# Power.net
KiCad netlist of a schematic drawn in Altium Designer
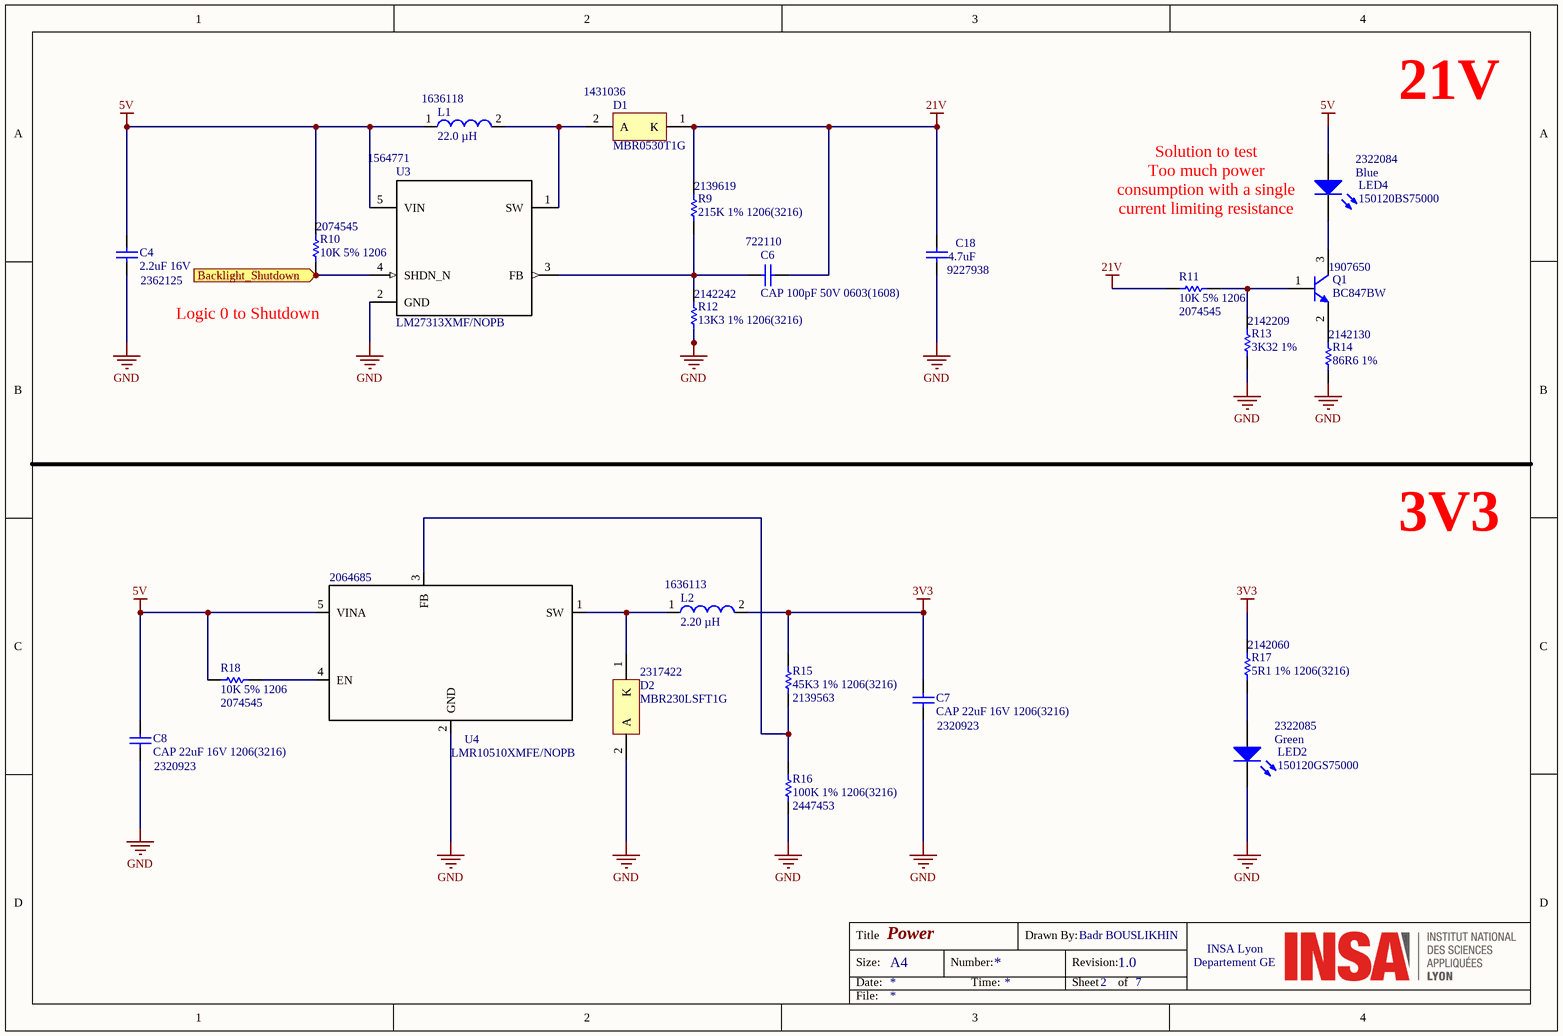
[diagram p0: Power.SchDoc]

(export (version "E")
  (design (tool "Eeschema 10.0.6"))
  (components
    (comp (ref "C4")
      (value "2.2uF 16V")
      (footprint "CAPC1206(3216)190_L")
      (description "CAP 2.2uF 16V ±20% 1206 (3216 Metric) Thickness 1.9mm SMD")
      (fields (field (name "TOLERANCE") "±20%") (field (name "SUPPLIER PART NUMBER 1") "2362125"))
      (libsource (lib "Altium Content Vault") (part "CMP-1037-04816-1"))
    )
    (comp (ref "C6")
      (value "CAP 100pF 50V 0603(1608)")
      (footprint "CAPC0603(1608)100_L")
      (description "CAP 100pF 50V ±10% 0603 (1608 Metric) Thickness 1mm SMD")
      (fields
        (field (name "TOLERANCE") "±10%")
        (field (name "SUPPLIER PART NUMBER 1") "722110")
        (field (name "MANUFACTURER") "YAGEO (PHYCOMP)")
      )
      (libsource (lib "Altium Content Vault") (part "CAP"))
    )
    (comp (ref "C7")
      (value "CAP 22uF 16V 1206(3216)")
      (footprint "CAPC1206(3216)190_N")
      (description "CAP 22uF 16V ±10% 1206 (3216 Metric) Thickness 1.9mm SMD")
      (fields (field (name "TOLERANCE") "±10%") (field (name "SUPPLIER PART NUMBER 1") "2320923"))
      (libsource (lib "Altium Content Vault") (part "CMP-1037-04992-1"))
    )
    (comp (ref "C8")
      (value "CAP 22uF 16V 1206(3216)")
      (footprint "CAPC1206(3216)190_N")
      (description "CAP 22uF 16V ±10% 1206 (3216 Metric) Thickness 1.9mm SMD")
      (fields (field (name "TOLERANCE") "±10%") (field (name "SUPPLIER PART NUMBER 1") "2320923"))
      (libsource (lib "Altium Content Vault") (part "CMP-1037-04992-1"))
    )
    (comp (ref "C18")
      (value "4.7uF")
      (footprint "CAPC1206(3216)190_N")
      (description "CAP 4.7uF 50V ±10% 1206 (3216 Metric) Thickness 1.9mm SMD")
      (fields (field (name "TOLERANCE") "±10%") (field (name "SUPPLIER PART NUMBER 1") "9227938"))
      (libsource (lib "Altium Content Vault") (part "CAP"))
    )
    (comp (ref "D1")
      (value "MBR0530T1G")
      (footprint "ONSC-SOD-123-2-425-04_V")
      (description "Schottky Power Rectifier, 2-Pin SOD-123, Pb-Free, Tape and Reel")
      (fields
        (field (name "MANUFACTURER") "On Semiconductor")
        (field (name "SUPPLIER PART NUMBER 1") "1431036")
      )
      (libsource (lib "Altium Content Vault") (part "CMP-1055-00413-1"))
    )
    (comp (ref "D2")
      (value "MBR230LSFT1G")
      (footprint "ONSC-SOD-123FL-2-498-01_V")
      (description "Schottky Power Rectifier, 2-Pin SOD-123, Pb-Free, Tape and Reel")
      (fields
        (field (name "MANUFACTURER") "On Semiconductor")
        (field (name "SUPPLIER PART NUMBER 1") "2317422")
      )
      (libsource (lib "Altium Content Vault") (part "CMP-1055-00442-1"))
    )
    (comp (ref "L1")
      (value "22.0 µH")
      (footprint "WE-PD4-S")
      (description "SMD-Power Inductor WE-PD4, L = 22.0 µH")
      (fields (field (name "SUPPLIER PART NUMBER 1") "1636118"))
      (libsource (lib "Altium Content Vault") (part "CMP-0227-00739-1"))
    )
    (comp (ref "L2")
      (value "2.20 µH")
      (footprint "WE-PD4-S")
      (description "SMD-Power Inductor WE-PD4, L = 2.20 µH")
      (fields
        (field (name "SUPPLIER PART NUMBER 1") "1636113")
        (field (name "MANUFACTURER") "WURTH ELEKTRONIK")
        (field (name "MANUFACTURER PART NUMBER") "74455022")
      )
      (libsource (lib "Altium Content Vault") (part "CMP-0227-00671-1"))
    )
    (comp (ref "LED2")
      (value "150120GS75000")
      (footprint "1206_A")
      (description "SMD mono-color Chip LED, WL-SMCW, Green")
      (fields
        (field (name "MANUFACTURER") "Wuerth Elektronik")
        (field (name "COLOR") "Green")
        (field (name "SUPPLIER PART NUMBER 1") "2322085")
      )
      (libsource (lib "Altium Content Vault") (part "CMP-1426-00014-1"))
    )
    (comp (ref "LED4")
      (value "150120BS75000")
      (footprint "1206_A")
      (description "SMD mono-color Chip LED, WL-SMCW, Blue")
      (fields
        (field (name "MANUFACTURER") "Wuerth Elektronik")
        (field (name "COLOR") "Blue")
        (field (name "SUPPLIER PART NUMBER 1") "2322084")
      )
      (libsource (lib "Altium Content Vault") (part "CMP-1426-00015-1"))
    )
    (comp (ref "Q1")
      (value "BC847BW")
      (footprint "INF-SOT323_N")
      (description "NPN Silicon AF Transistor, 45 V VCEO, 100 mA IC, SOT323, Reel, Green")
      (fields (field (name "MANUFACTURER") "Infineon") (field (name "SUPPLIER PART NUMBER 1") "1907650"))
      (libsource (lib "Altium Content Vault") (part "INF-BJTNPN-BEC-3"))
    )
    (comp (ref "R9")
      (value "215K 1% 1206(3216)")
      (footprint "RESC1206(3216)_M")
      (description "215K 0.25W 1% 1206 (3216 Metric)  SMD")
      (fields
        (field (name "TOLERANCE") "1 %")
        (field (name "POWER") "0.25 W")
        (field (name "SUPPLIER PART NUMBER 1") "2139619")
      )
      (libsource (lib "Altium Content Vault") (part "RES"))
    )
    (comp (ref "R10")
      (value "10K 5% 1206")
      (footprint "RESC1206(3216)_M")
      (description "10K 0.25W 5% 1206 (3216 Metric)  SMD")
      (fields
        (field (name "POWER") "0.25 W")
        (field (name "TOLERANCE") "5 %")
        (field (name "SUPPLIER PART NUMBER 1") "2074545")
      )
      (libsource (lib "Altium Content Vault") (part "CMP-1014-00098-1"))
    )
    (comp (ref "R11")
      (value "10K 5% 1206")
      (footprint "RESC1206(3216)_M")
      (description "10K 0.25W 5% 1206 (3216 Metric)  SMD")
      (fields
        (field (name "POWER") "0.25 W")
        (field (name "TOLERANCE") "5 %")
        (field (name "SUPPLIER PART NUMBER 1") "2074545")
      )
      (libsource (lib "Altium Content Vault") (part "CMP-1014-00098-1"))
    )
    (comp (ref "R12")
      (value "13K3 1% 1206(3216)")
      (footprint "RESC1206(3216)_L")
      (description "13K3 0.25W 1% 1206 (3216 Metric)  SMD")
      (fields
        (field (name "TOLERANCE") "1 %")
        (field (name "POWER") "0.25 W")
        (field (name "SUPPLIER PART NUMBER 1") "2142242")
      )
      (libsource (lib "Altium Content Vault") (part "RES"))
    )
    (comp (ref "R13")
      (value "3K32 1%")
      (footprint "RESC1206(3216)_L")
      (description "3K32 0.25W 1% 1206 (3216 Metric)  SMD")
      (fields
        (field (name "TOLERANCE") "1 %")
        (field (name "POWER") "0.25 W")
        (field (name "SUPPLIER PART NUMBER 1") "2142209")
      )
      (libsource (lib "Altium Content Vault") (part "RES"))
    )
    (comp (ref "R14")
      (value "86R6 1%")
      (footprint "RESC1206(3216)_N")
      (description "86R6 0.25W 1% 1206 (3216 Metric)  SMD")
      (fields
        (field (name "TOLERANCE") "1 %")
        (field (name "POWER") "0.25 W")
        (field (name "SUPPLIER PART NUMBER 1") "2142130")
      )
      (libsource (lib "Altium Content Vault") (part "RES"))
    )
    (comp (ref "R15")
      (value "45K3 1% 1206(3216)")
      (footprint "RESC1206(3216)_L")
      (description "45K3 0.25W 1% 1206 (3216 Metric)  SMD")
      (fields
        (field (name "TOLERANCE") "1 %")
        (field (name "POWER") "0.25 W")
        (field (name "SUPPLIER PART NUMBER 1") "2139563")
      )
      (libsource (lib "Altium Content Vault") (part "RES"))
    )
    (comp (ref "R16")
      (value "100K 1% 1206(3216)")
      (footprint "RESC1206(3216)_L")
      (description "100K 0.25W 1% 1206 (3216 Metric)  SMD")
      (fields
        (field (name "TOLERANCE") "1 %")
        (field (name "POWER") "0.25 W")
        (field (name "SUPPLIER PART NUMBER 1") "2447453")
      )
      (libsource (lib "Altium Content Vault") (part "RES"))
    )
    (comp (ref "R17")
      (value "5R1 1% 1206(3216)")
      (footprint "RESC1206(3216)_N")
      (description "5R1 0.25W 1% 1206 (3216 Metric)  SMD")
      (fields
        (field (name "TOLERANCE") "1 %")
        (field (name "POWER") "0.25 W")
        (field (name "SUPPLIER PART NUMBER 1") "2142060")
      )
      (libsource (lib "Altium Content Vault") (part "RES"))
    )
    (comp (ref "R18")
      (value "10K 5% 1206")
      (footprint "RESC1206(3216)_M")
      (description "10K 0.25W 5% 1206 (3216 Metric)  SMD")
      (fields
        (field (name "POWER") "0.25 W")
        (field (name "TOLERANCE") "5 %")
        (field (name "SUPPLIER PART NUMBER 1") "2074545")
      )
      (libsource (lib "Altium Content Vault") (part "CMP-1014-00098-1"))
    )
    (comp (ref "U3")
      (value "LM27313XMF/NOPB")
      (footprint "DBV0005A")
      (description "Imported")
      (fields
        (field (name "PARTNUMBER") "LM27313XQMF/NOPB")
        (field (name "MANUFACTURER") "Texas Instruments")
        (field (name "SUPPLIER PART NUMBER 1") "1564771")
      )
      (libsource (lib "LM27313") (part "LM27313XMF/NOPB"))
    )
    (comp (ref "U4")
      (value "LMR10510XMFE/NOPB")
      (footprint "DBV0005A")
      (description "Imported")
      (fields
        (field (name "SUPPLIER PART NUMBER 1") "2064685")
        (field (name "MANUFACTURER") "TEXAS INSTRUMENTS")
        (field (name "MANUFACTURER PART NUMBER") "LMR10510XMF")
      )
      (libsource (lib "LMR10510") (part "LMR10510XMFE/NOPB"))
    )
  )
  (nets
    (net (code "1") (name "/Backlight_Shutdown") (class "Default")
      (node (ref "R10") (pin "1") (pinfunction "1_1") (pintype "passive"))
      (node (ref "U3") (pin "4") (pinfunction "SHDN_N_4") (pintype "input"))
    )
    (net (code "2") (name "3V3") (class "Default")
      (node (ref "C7") (pin "2") (pinfunction "2_2") (pintype "passive"))
      (node (ref "L2") (pin "2") (pinfunction "2_2") (pintype "passive"))
      (node (ref "R15") (pin "1") (pinfunction "1_1") (pintype "passive"))
      (node (ref "R17") (pin "2") (pinfunction "2_2") (pintype "passive"))
    )
    (net (code "3") (name "5V") (class "Default")
      (node (ref "C4") (pin "2") (pinfunction "2_2") (pintype "passive"))
      (node (ref "C8") (pin "2") (pinfunction "2_2") (pintype "passive"))
      (node (ref "L1") (pin "1") (pinfunction "1_1") (pintype "passive"))
      (node (ref "LED4") (pin "2") (pinfunction "A_2") (pintype "passive"))
      (node (ref "R10") (pin "2") (pinfunction "2_2") (pintype "passive"))
      (node (ref "R18") (pin "2") (pinfunction "2_2") (pintype "passive"))
      (node (ref "U3") (pin "5") (pinfunction "VIN_5") (pintype "power_in"))
      (node (ref "U4") (pin "5") (pinfunction "VINA_5") (pintype "passive"))
    )
    (net (code "4") (name "21V") (class "Default")
      (node (ref "C18") (pin "2") (pinfunction "2_2") (pintype "passive"))
      (node (ref "C6") (pin "2") (pinfunction "2_2") (pintype "passive"))
      (node (ref "D1") (pin "1") (pinfunction "K_1") (pintype "passive"))
      (node (ref "R11") (pin "2") (pinfunction "2_2") (pintype "passive"))
      (node (ref "R9") (pin "2") (pinfunction "2_2") (pintype "passive"))
    )
    (net (code "5") (name "GND") (class "Default")
      (node (ref "C18") (pin "1") (pinfunction "1_1") (pintype "passive"))
      (node (ref "C4") (pin "1") (pinfunction "1_1") (pintype "passive"))
      (node (ref "C7") (pin "1") (pinfunction "1_1") (pintype "passive"))
      (node (ref "C8") (pin "1") (pinfunction "1_1") (pintype "passive"))
      (node (ref "D2") (pin "2") (pinfunction "A_2") (pintype "passive"))
      (node (ref "LED2") (pin "1") (pinfunction "K_1") (pintype "passive"))
      (node (ref "R12") (pin "1") (pinfunction "1_1") (pintype "passive"))
      (node (ref "R13") (pin "1") (pinfunction "1_1") (pintype "passive"))
      (node (ref "R14") (pin "1") (pinfunction "1_1") (pintype "passive"))
      (node (ref "R16") (pin "1") (pinfunction "1_1") (pintype "passive"))
      (node (ref "U3") (pin "2") (pinfunction "GND_2") (pintype "power_in"))
      (node (ref "U4") (pin "2") (pinfunction "GND_2") (pintype "passive"))
    )
    (net (code "6") (name "Net-(D1-A)") (class "Default")
      (node (ref "D1") (pin "2") (pinfunction "A_2") (pintype "passive"))
      (node (ref "L1") (pin "2") (pinfunction "2_2") (pintype "passive"))
      (node (ref "U3") (pin "1") (pinfunction "SW_1") (pintype "power_in"))
    )
    (net (code "7") (name "Net-(D2-K)") (class "Default")
      (node (ref "D2") (pin "1") (pinfunction "K_1") (pintype "passive"))
      (node (ref "L2") (pin "1") (pinfunction "1_1") (pintype "passive"))
      (node (ref "U4") (pin "1") (pinfunction "SW_1") (pintype "passive"))
    )
    (net (code "8") (name "Net-(LED2-A)") (class "Default")
      (node (ref "LED2") (pin "2") (pinfunction "A_2") (pintype "passive"))
      (node (ref "R17") (pin "1") (pinfunction "1_1") (pintype "passive"))
    )
    (net (code "9") (name "Net-(LED4-K)") (class "Default")
      (node (ref "LED4") (pin "1") (pinfunction "K_1") (pintype "passive"))
      (node (ref "Q1") (pin "3") (pinfunction "C_3") (pintype "passive"))
    )
    (net (code "10") (name "Net-(Q1-B)") (class "Default")
      (node (ref "Q1") (pin "1") (pinfunction "B_1") (pintype "passive"))
      (node (ref "R11") (pin "1") (pinfunction "1_1") (pintype "passive"))
      (node (ref "R13") (pin "2") (pinfunction "2_2") (pintype "passive"))
    )
    (net (code "11") (name "Net-(Q1-E)") (class "Default")
      (node (ref "Q1") (pin "2") (pinfunction "E_2") (pintype "passive"))
      (node (ref "R14") (pin "2") (pinfunction "2_2") (pintype "passive"))
    )
    (net (code "12") (name "Net-(U3-FB)") (class "Default")
      (node (ref "C6") (pin "1") (pinfunction "1_1") (pintype "passive"))
      (node (ref "R12") (pin "2") (pinfunction "2_2") (pintype "passive"))
      (node (ref "R9") (pin "1") (pinfunction "1_1") (pintype "passive"))
      (node (ref "U3") (pin "3") (pinfunction "FB_3") (pintype "output"))
    )
    (net (code "13") (name "Net-(U4-EN)") (class "Default")
      (node (ref "R18") (pin "1") (pinfunction "1_1") (pintype "passive"))
      (node (ref "U4") (pin "4") (pinfunction "EN_4") (pintype "passive"))
    )
    (net (code "14") (name "Net-(U4-FB)") (class "Default")
      (node (ref "R15") (pin "2") (pinfunction "2_2") (pintype "passive"))
      (node (ref "R16") (pin "2") (pinfunction "2_2") (pintype "passive"))
      (node (ref "U4") (pin "3") (pinfunction "FB_3") (pintype "passive"))
    )
  )
)
